# leoTracker_Boost.net
KiCad netlist of a schematic drawn in EAGLE
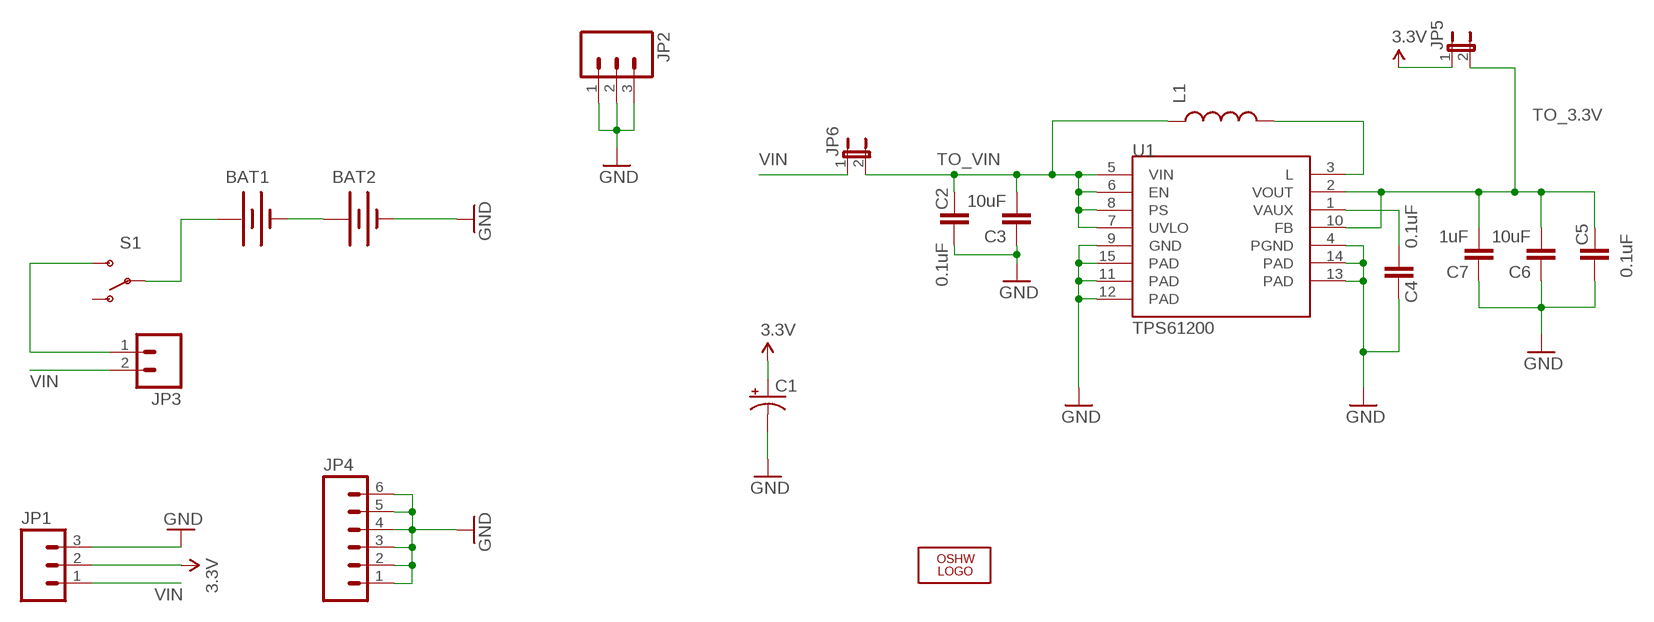
[diagram p0: schematic, sheet 1]

(export (version "E")
  (design (tool "Eeschema 10.0.6"))
  (components
    (comp (ref "BAT1")
      (value "BATTERYAA")
      (footprint "eagle-import:BATTERY-AA")
      (libsource (lib "eagle-import") (part "BATTERYAA"))
    )
    (comp (ref "BAT2")
      (value "BATTERYAA")
      (footprint "eagle-import:BATTERY-AA")
      (libsource (lib "eagle-import") (part "BATTERYAA"))
    )
    (comp (ref "C1")
      (value "CAP_POL1206")
      (footprint "eagle-import:EIA3216")
      (libsource (lib "eagle-import") (part "CAP_POL1206"))
    )
    (comp (ref "C2")
      (value "0.1uF")
      (footprint "eagle-import:0805")
      (libsource (lib "eagle-import") (part "CAP0805"))
    )
    (comp (ref "C3")
      (value "10uF")
      (footprint "eagle-import:0805")
      (libsource (lib "eagle-import") (part "CAP0805"))
    )
    (comp (ref "C4")
      (value "0.1uF")
      (footprint "eagle-import:0805")
      (libsource (lib "eagle-import") (part "CAP0805"))
    )
    (comp (ref "C5")
      (value "0.1uF")
      (footprint "eagle-import:0805")
      (libsource (lib "eagle-import") (part "CAP0805"))
    )
    (comp (ref "C6")
      (value "10uF")
      (footprint "eagle-import:0805")
      (libsource (lib "eagle-import") (part "CAP0805"))
    )
    (comp (ref "C7")
      (value "1uF")
      (footprint "eagle-import:0805")
      (libsource (lib "eagle-import") (part "CAP0805"))
    )
    (comp (ref "JP1")
      (value "M03LOCK")
      (footprint "eagle-import:1X03_LOCK")
      (libsource (lib "eagle-import") (part "M03LOCK"))
    )
    (comp (ref "JP2")
      (value "M03LOCK")
      (footprint "eagle-import:1X03_LOCK")
      (libsource (lib "eagle-import") (part "M03LOCK"))
    )
    (comp (ref "JP3")
      (value "M02LOCK")
      (footprint "eagle-import:1X02_LOCK")
      (libsource (lib "eagle-import") (part "M02LOCK"))
    )
    (comp (ref "JP4")
      (value "M06LOCK")
      (footprint "eagle-import:1X06_LOCK")
      (libsource (lib "eagle-import") (part "M06LOCK"))
    )
    (comp (ref "JP5")
      (value "JUMPER-2SMD-NC")
      (footprint "eagle-import:SJ_2S")
      (libsource (lib "eagle-import") (part "JUMPER-2SMD-NC"))
    )
    (comp (ref "JP6")
      (value "JUMPER-2SMD-NC")
      (footprint "eagle-import:SJ_2S")
      (libsource (lib "eagle-import") (part "JUMPER-2SMD-NC"))
    )
    (comp (ref "L1")
      (value "INDUCTOR.")
      (footprint "eagle-import:CDRH2D09")
      (libsource (lib "eagle-import") (part "INDUCTOR."))
    )
    (comp (ref "LOGO2")
      (value "OSHW_LOGO_6MILX0100-NT")
      (footprint "eagle-import:OSHW_6X100_NOTEXT")
      (libsource (lib "eagle-import") (part "OSHW_LOGO_6MILX0100-NT"))
    )
    (comp (ref "S1")
      (value "SWITCH-SPDTPTH")
      (footprint "eagle-import:SWITCH-SPDT")
      (libsource (lib "eagle-import") (part "SWITCH-SPDTPTH"))
    )
    (comp (ref "U1")
      (value "TPS61200")
      (footprint "eagle-import:QFN-10_PAD")
      (libsource (lib "eagle-import") (part "TPS61200"))
    )
  )
  (nets
    (net (code "1") (name "/TO_3.3V") (class "Default")
      (node (ref "C5") (pin "1") (pinfunction "1_1") (pintype "passive"))
      (node (ref "C6") (pin "2") (pinfunction "2_2") (pintype "passive"))
      (node (ref "C7") (pin "2") (pinfunction "2_2") (pintype "passive"))
      (node (ref "JP5") (pin "2") (pinfunction "2_2") (pintype "passive"))
      (node (ref "U1") (pin "10") (pinfunction "FB_10") (pintype "passive"))
      (node (ref "U1") (pin "2") (pinfunction "VOUT_2") (pintype "passive"))
    )
    (net (code "2") (name "/TO_VIN") (class "Default")
      (node (ref "C2") (pin "1") (pinfunction "1_1") (pintype "passive"))
      (node (ref "C3") (pin "2") (pinfunction "2_2") (pintype "passive"))
      (node (ref "JP6") (pin "2") (pinfunction "2_2") (pintype "passive"))
      (node (ref "L1") (pin "P$1") (pinfunction "1_P$1") (pintype "passive"))
      (node (ref "U1") (pin "5") (pinfunction "VIN_5") (pintype "power_in"))
      (node (ref "U1") (pin "6") (pinfunction "EN_6") (pintype "input"))
      (node (ref "U1") (pin "7") (pinfunction "UVLO_7") (pintype "passive"))
      (node (ref "U1") (pin "8") (pinfunction "PS_8") (pintype "input"))
    )
    (net (code "3") (name "/VIN") (class "Default")
      (node (ref "JP1") (pin "1") (pinfunction "1_1") (pintype "passive"))
      (node (ref "JP3") (pin "2") (pinfunction "2_2") (pintype "passive"))
      (node (ref "JP6") (pin "1") (pinfunction "1_1") (pintype "passive"))
    )
    (net (code "4") (name "3.3V") (class "Default")
      (node (ref "C1") (pin "A") (pinfunction "+_A") (pintype "passive"))
      (node (ref "JP1") (pin "2") (pinfunction "2_2") (pintype "passive"))
      (node (ref "JP5") (pin "1") (pinfunction "1_1") (pintype "passive"))
    )
    (net (code "5") (name "GND") (class "Default")
      (node (ref "BAT2") (pin "GND@1") (pinfunction "-_GND@1") (pintype "power_in"))
      (node (ref "C1") (pin "C") (pinfunction "-_C") (pintype "passive"))
      (node (ref "C2") (pin "2") (pinfunction "2_2") (pintype "passive"))
      (node (ref "C3") (pin "1") (pinfunction "1_1") (pintype "passive"))
      (node (ref "C4") (pin "1") (pinfunction "1_1") (pintype "passive"))
      (node (ref "C5") (pin "2") (pinfunction "2_2") (pintype "passive"))
      (node (ref "C6") (pin "1") (pinfunction "1_1") (pintype "passive"))
      (node (ref "C7") (pin "1") (pinfunction "1_1") (pintype "passive"))
      (node (ref "JP1") (pin "3") (pinfunction "3_3") (pintype "passive"))
      (node (ref "JP2") (pin "1") (pinfunction "1_1") (pintype "passive"))
      (node (ref "JP2") (pin "2") (pinfunction "2_2") (pintype "passive"))
      (node (ref "JP2") (pin "3") (pinfunction "3_3") (pintype "passive"))
      (node (ref "JP4") (pin "1") (pinfunction "1_1") (pintype "passive"))
      (node (ref "JP4") (pin "2") (pinfunction "2_2") (pintype "passive"))
      (node (ref "JP4") (pin "3") (pinfunction "3_3") (pintype "passive"))
      (node (ref "JP4") (pin "4") (pinfunction "4_4") (pintype "passive"))
      (node (ref "JP4") (pin "5") (pinfunction "5_5") (pintype "passive"))
      (node (ref "JP4") (pin "6") (pinfunction "6_6") (pintype "passive"))
      (node (ref "U1") (pin "11") (pinfunction "PAD_11") (pintype "power_in"))
      (node (ref "U1") (pin "12") (pinfunction "PAD_12") (pintype "power_in"))
      (node (ref "U1") (pin "13") (pinfunction "PAD_13") (pintype "power_in"))
      (node (ref "U1") (pin "14") (pinfunction "PAD_14") (pintype "power_in"))
      (node (ref "U1") (pin "15") (pinfunction "PAD_15") (pintype "power_in"))
      (node (ref "U1") (pin "4") (pinfunction "PGND_4") (pintype "power_in"))
      (node (ref "U1") (pin "9") (pinfunction "GND_9") (pintype "power_in"))
    )
    (net (code "6") (name "Net-(BAT1-+)") (class "Default")
      (node (ref "BAT1") (pin "PWR@1") (pinfunction "+_PWR@1") (pintype "power_in"))
      (node (ref "S1") (pin "2") (pinfunction "P_2") (pintype "passive"))
    )
    (net (code "7") (name "Net-(BAT1--)") (class "Default")
      (node (ref "BAT1") (pin "GND@1") (pinfunction "-_GND@1") (pintype "power_in"))
      (node (ref "BAT2") (pin "PWR@1") (pinfunction "+_PWR@1") (pintype "power_in"))
    )
    (net (code "8") (name "Net-(L1-2)") (class "Default")
      (node (ref "L1") (pin "P$2") (pinfunction "2_P$2") (pintype "passive"))
      (node (ref "U1") (pin "3") (pinfunction "L_3") (pintype "passive"))
    )
    (net (code "9") (name "Net-(S1-S)") (class "Default")
      (node (ref "JP3") (pin "1") (pinfunction "1_1") (pintype "passive"))
      (node (ref "S1") (pin "3") (pinfunction "S_3") (pintype "passive"))
    )
    (net (code "10") (name "Net-(U1-VAUX)") (class "Default")
      (node (ref "C4") (pin "2") (pinfunction "2_2") (pintype "passive"))
      (node (ref "U1") (pin "1") (pinfunction "VAUX_1") (pintype "passive"))
    )
    (net (code "11") (name "unconnected-(S1-O-Pad1)") (class "Default")
      (node (ref "S1") (pin "1") (pinfunction "O_1") (pintype "passive"))
    )
  )
)
